# LMT01-PCB.net
KiCad netlist of a schematic drawn in EAGLE
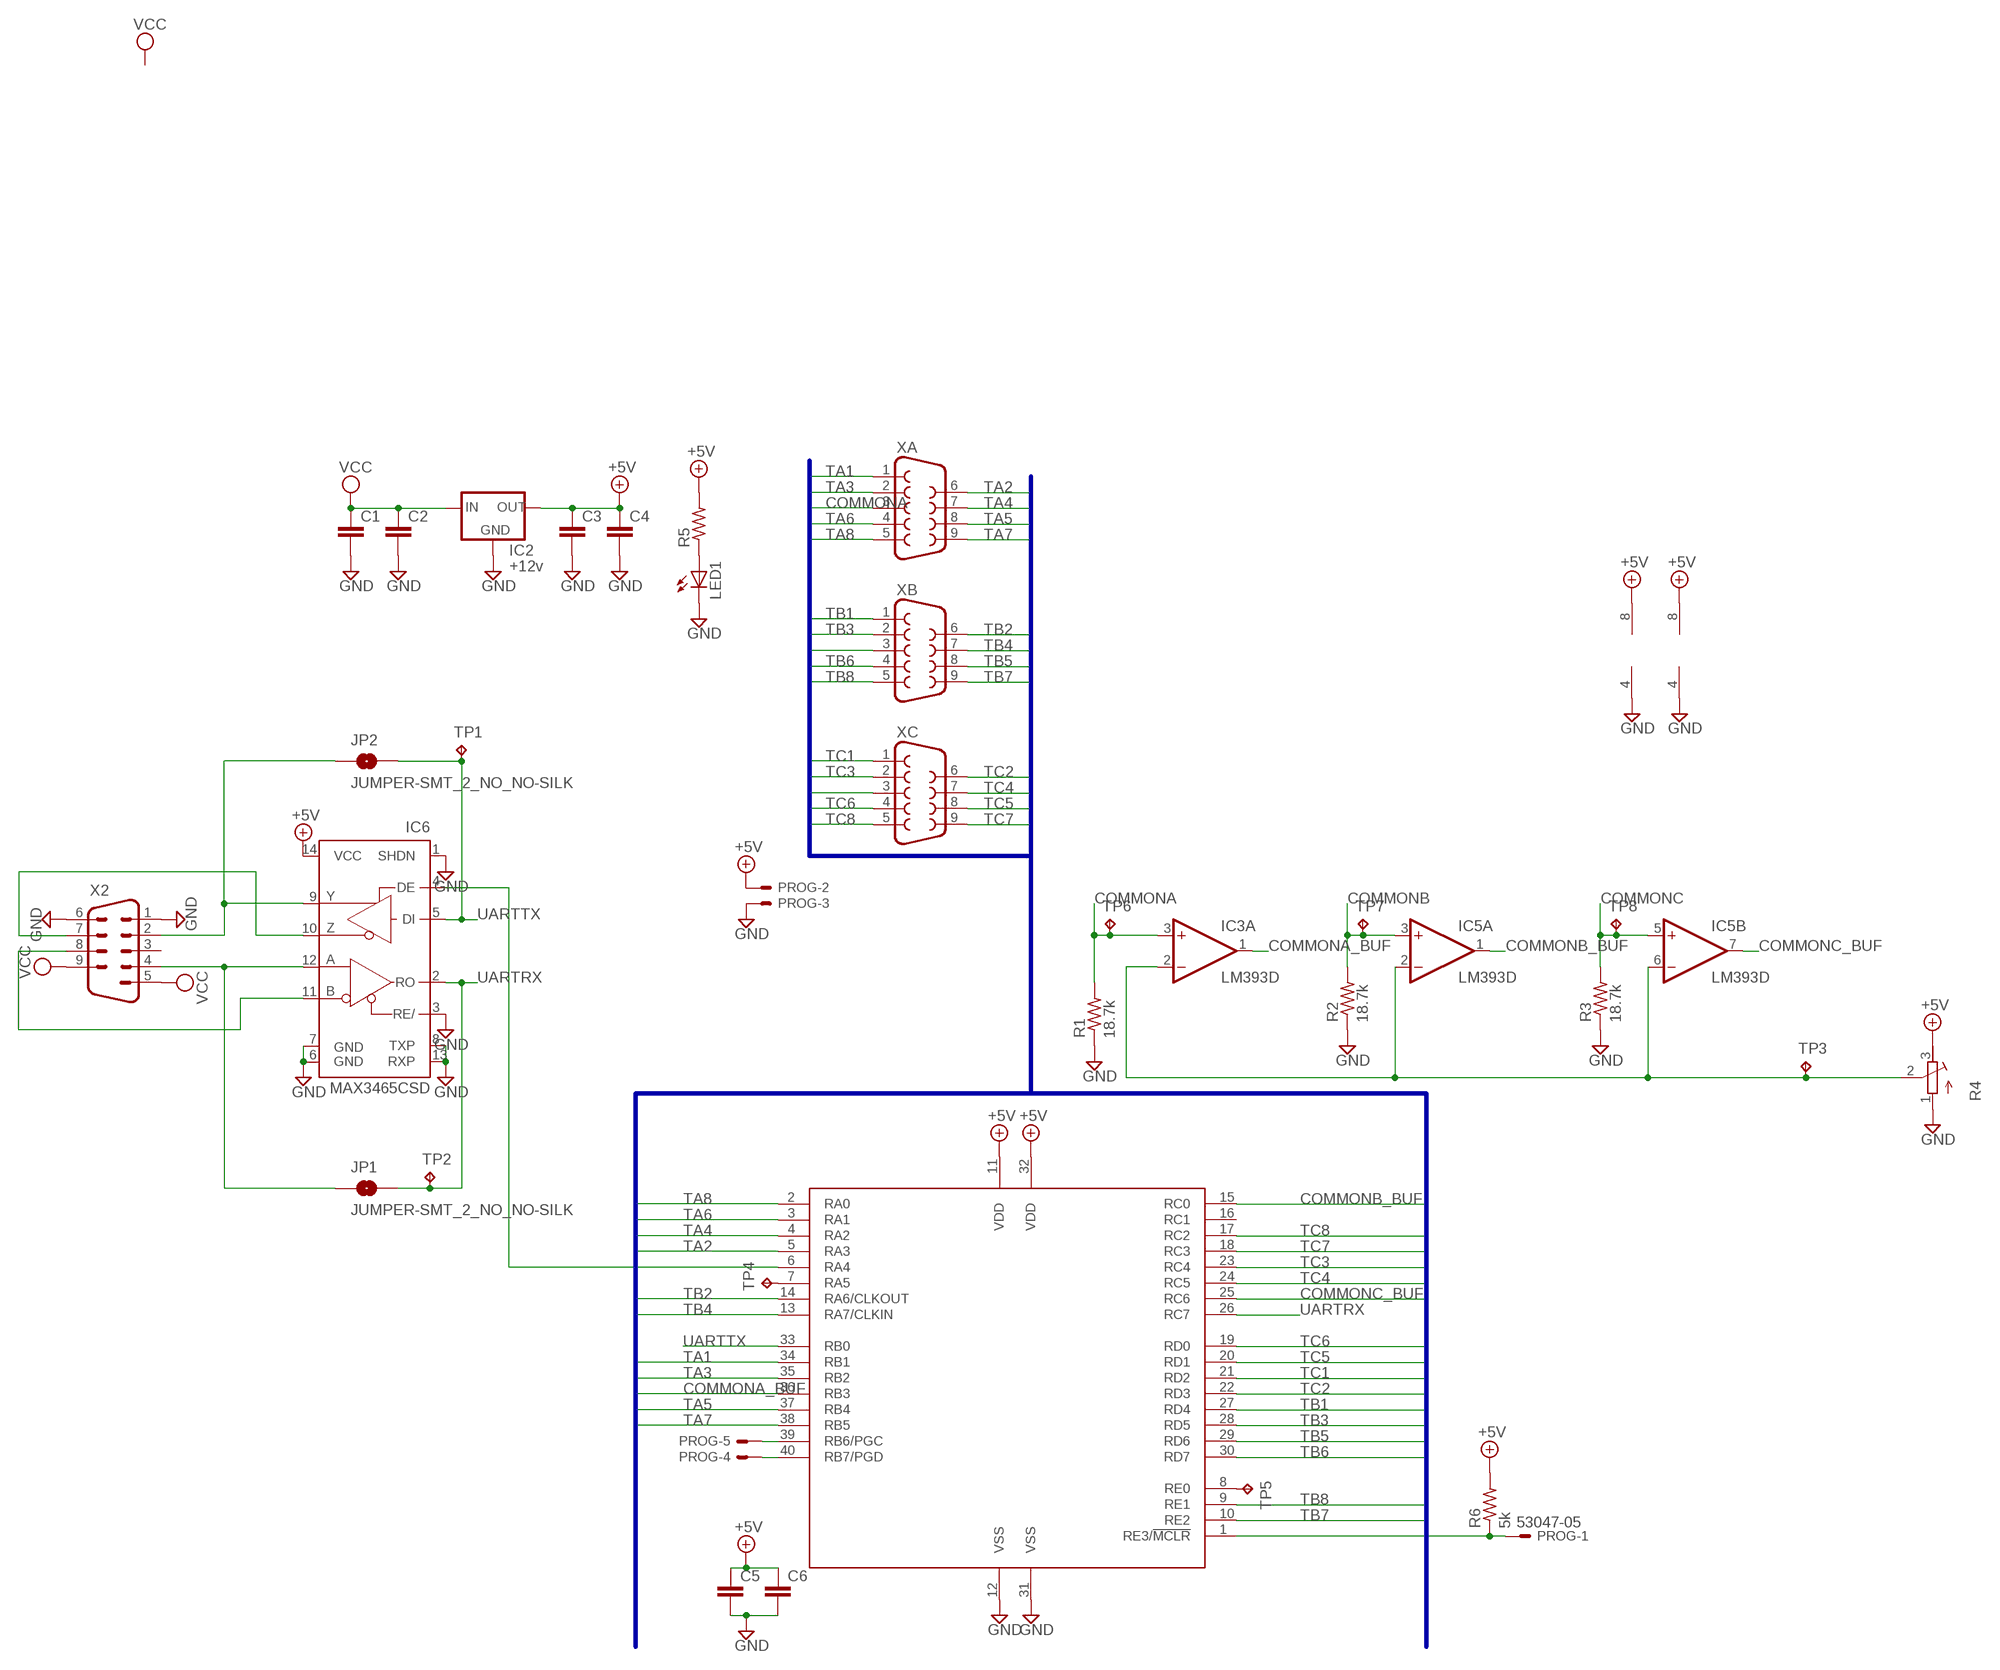
[diagram p0: schematic, sheet 1]

(export (version "E")
  (design (tool "Eeschema 10.0.6"))
  (components
    (comp (ref "C1")
      (value "C-EUC1206")
      (footprint "eagle-import:C1206")
      (libsource (lib "eagle-import") (part "C-EUC1206"))
    )
    (comp (ref "C2")
      (value "C-EUC1206")
      (footprint "eagle-import:C1206")
      (libsource (lib "eagle-import") (part "C-EUC1206"))
    )
    (comp (ref "C3")
      (value "C-EUC1206")
      (footprint "eagle-import:C1206")
      (libsource (lib "eagle-import") (part "C-EUC1206"))
    )
    (comp (ref "C4")
      (value "C-EUC1206")
      (footprint "eagle-import:C1206")
      (libsource (lib "eagle-import") (part "C-EUC1206"))
    )
    (comp (ref "C5")
      (value "C-EUC1206")
      (footprint "eagle-import:C1206")
      (libsource (lib "eagle-import") (part "C-EUC1206"))
    )
    (comp (ref "C6")
      (value "C-EUC1206")
      (footprint "eagle-import:C1206")
      (libsource (lib "eagle-import") (part "C-EUC1206"))
    )
    (comp (ref "IC1")
      (value "PIC18F47Q84")
      (footprint "eagle-import:DIL40")
      (libsource (lib "eagle-import") (part "PIC18F47Q84"))
    )
    (comp (ref "IC2")
      (value "+12v")
      (footprint "eagle-import:TO-252")
      (libsource (lib "eagle-import") (part "V_REG_78XX7812"))
    )
    (comp (ref "IC3")
      (value "LM393D")
      (footprint "eagle-import:SO08")
      (libsource (lib "eagle-import") (part "LM393D"))
    )
    (comp (ref "IC5")
      (value "LM393D")
      (footprint "eagle-import:SO08")
      (libsource (lib "eagle-import") (part "LM393D"))
    )
    (comp (ref "IC6")
      (value "MAX3465CSD")
      (footprint "eagle-import:SO14")
      (fields (field (name "MPN") "MAX3465CSD+"))
      (libsource (lib "eagle-import") (part "MAX346SD5C"))
    )
    (comp (ref "JP1")
      (value "JUMPER-SMT_2_NO_NO-SILK")
      (footprint "eagle-import:SMT-JUMPER_2_NO_NO-SILK")
      (libsource (lib "eagle-import") (part "JUMPER-SMT_2_NO_NO-SILK"))
    )
    (comp (ref "JP2")
      (value "JUMPER-SMT_2_NO_NO-SILK")
      (footprint "eagle-import:SMT-JUMPER_2_NO_NO-SILK")
      (libsource (lib "eagle-import") (part "JUMPER-SMT_2_NO_NO-SILK"))
    )
    (comp (ref "LED1")
      (value "LEDCHIPLED_1206")
      (footprint "eagle-import:CHIPLED_1206")
      (libsource (lib "eagle-import") (part "LEDCHIPLED_1206"))
    )
    (comp (ref "PROG")
      (value "53047-05")
      (footprint "eagle-import:53047-05")
      (fields (field (name "MF") "MOLEX") (field (name "MPN") "53047-0510"))
      (libsource (lib "eagle-import") (part "53?-05047"))
    )
    (comp (ref "R1")
      (value "18.7k")
      (footprint "eagle-import:R1206")
      (libsource (lib "eagle-import") (part "R-US_R1206"))
    )
    (comp (ref "R2")
      (value "18.7k")
      (footprint "eagle-import:R1206")
      (libsource (lib "eagle-import") (part "R-US_R1206"))
    )
    (comp (ref "R3")
      (value "18.7k")
      (footprint "eagle-import:R1206")
      (libsource (lib "eagle-import") (part "R-US_R1206"))
    )
    (comp (ref "R4")
      (value "R-TRIMM4G/J")
      (footprint "eagle-import:RTRIM4G_J")
      (libsource (lib "eagle-import") (part "R-TRIMM4G/J"))
    )
    (comp (ref "R5")
      (value "R-US_R1206")
      (footprint "eagle-import:R1206")
      (libsource (lib "eagle-import") (part "R-US_R1206"))
    )
    (comp (ref "R6")
      (value "5k")
      (footprint "eagle-import:R1206")
      (libsource (lib "eagle-import") (part "R-US_R1206"))
    )
    (comp (ref "TP1")
      (value "TPB1,27")
      (footprint "eagle-import:B1,27")
      (libsource (lib "eagle-import") (part "TPB1,27"))
    )
    (comp (ref "TP2")
      (value "TPB1,27")
      (footprint "eagle-import:B1,27")
      (libsource (lib "eagle-import") (part "TPB1,27"))
    )
    (comp (ref "TP3")
      (value "TPB1,27")
      (footprint "eagle-import:B1,27")
      (libsource (lib "eagle-import") (part "TPB1,27"))
    )
    (comp (ref "TP4")
      (value "TPB1,27")
      (footprint "eagle-import:B1,27")
      (libsource (lib "eagle-import") (part "TPB1,27"))
    )
    (comp (ref "TP5")
      (value "TPB1,27")
      (footprint "eagle-import:B1,27")
      (libsource (lib "eagle-import") (part "TPB1,27"))
    )
    (comp (ref "TP6")
      (value "TPB1,27")
      (footprint "eagle-import:B1,27")
      (libsource (lib "eagle-import") (part "TPB1,27"))
    )
    (comp (ref "TP7")
      (value "TPB1,27")
      (footprint "eagle-import:B1,27")
      (libsource (lib "eagle-import") (part "TPB1,27"))
    )
    (comp (ref "TP8")
      (value "TPB1,27")
      (footprint "eagle-import:B1,27")
      (libsource (lib "eagle-import") (part "TPB1,27"))
    )
    (comp (ref "X2")
      (value "M09HP")
      (footprint "eagle-import:M09HP")
      (libsource (lib "eagle-import") (part "M09HP"))
    )
    (comp (ref "XA")
      (value "F09HP")
      (footprint "eagle-import:F09HP")
      (libsource (lib "eagle-import") (part "F09HP"))
    )
    (comp (ref "XB")
      (value "F09HP")
      (footprint "eagle-import:F09HP")
      (libsource (lib "eagle-import") (part "F09HP"))
    )
    (comp (ref "XC")
      (value "F09HP")
      (footprint "eagle-import:F09HP")
      (libsource (lib "eagle-import") (part "F09HP"))
    )
  )
  (nets
    (net (code "1") (name "+5V") (class "Default")
      (node (ref "C3") (pin "1") (pinfunction "1_1") (pintype "passive"))
      (node (ref "C4") (pin "1") (pinfunction "1_1") (pintype "passive"))
      (node (ref "C5") (pin "1") (pinfunction "1_1") (pintype "passive"))
      (node (ref "C6") (pin "1") (pinfunction "1_1") (pintype "passive"))
      (node (ref "IC1") (pin "11") (pinfunction "VDD_11") (pintype "bidirectional"))
      (node (ref "IC1") (pin "32") (pinfunction "VDD_32") (pintype "bidirectional"))
      (node (ref "IC2") (pin "2") (pinfunction "OUT_2") (pintype "passive"))
      (node (ref "IC3") (pin "8") (pinfunction "V+_8") (pintype "power_in"))
      (node (ref "IC5") (pin "8") (pinfunction "V+_8") (pintype "power_in"))
      (node (ref "IC6") (pin "14") (pinfunction "VCC_14") (pintype "power_in"))
      (node (ref "PROG") (pin "2") (pinfunction "S_2") (pintype "passive"))
      (node (ref "R4") (pin "3") (pinfunction "E_3") (pintype "passive"))
      (node (ref "R5") (pin "2") (pinfunction "2_2") (pintype "passive"))
      (node (ref "R6") (pin "2") (pinfunction "2_2") (pintype "passive"))
    )
    (net (code "2") (name "/COMMONA") (class "Default")
      (node (ref "IC3") (pin "3") (pinfunction "+IN_3") (pintype "input"))
      (node (ref "R1") (pin "2") (pinfunction "2_2") (pintype "passive"))
      (node (ref "TP6") (pin "TP") (pinfunction "TP_TP") (pintype "input"))
      (node (ref "XA") (pin "3") (pinfunction "3_3") (pintype "passive"))
    )
    (net (code "3") (name "/COMMONA_BUF") (class "Default")
      (node (ref "IC1") (pin "36") (pinfunction "RB3_36") (pintype "bidirectional"))
      (node (ref "IC3") (pin "1") (pinfunction "OUT_1") (pintype "output"))
    )
    (net (code "4") (name "/COMMONB") (class "Default")
      (node (ref "IC5") (pin "3") (pinfunction "+IN_3") (pintype "input"))
      (node (ref "R2") (pin "2") (pinfunction "2_2") (pintype "passive"))
      (node (ref "TP7") (pin "TP") (pinfunction "TP_TP") (pintype "input"))
      (node (ref "XB") (pin "3") (pinfunction "3_3") (pintype "passive"))
    )
    (net (code "5") (name "/COMMONB_BUF") (class "Default")
      (node (ref "IC1") (pin "15") (pinfunction "RC0_15") (pintype "bidirectional"))
      (node (ref "IC5") (pin "1") (pinfunction "OUT_1") (pintype "output"))
    )
    (net (code "6") (name "/COMMONC") (class "Default")
      (node (ref "IC5") (pin "5") (pinfunction "+IN_5") (pintype "input"))
      (node (ref "R3") (pin "2") (pinfunction "2_2") (pintype "passive"))
      (node (ref "TP8") (pin "TP") (pinfunction "TP_TP") (pintype "input"))
      (node (ref "XC") (pin "3") (pinfunction "3_3") (pintype "passive"))
    )
    (net (code "7") (name "/COMMONC_BUF") (class "Default")
      (node (ref "IC1") (pin "25") (pinfunction "RC6_25") (pintype "bidirectional"))
      (node (ref "IC5") (pin "7") (pinfunction "OUT_7") (pintype "output"))
    )
    (net (code "8") (name "/TA1") (class "Default")
      (node (ref "IC1") (pin "34") (pinfunction "RB1_34") (pintype "bidirectional"))
      (node (ref "XA") (pin "1") (pinfunction "1_1") (pintype "passive"))
    )
    (net (code "9") (name "/TA2") (class "Default")
      (node (ref "IC1") (pin "5") (pinfunction "RA3_5") (pintype "bidirectional"))
      (node (ref "XA") (pin "6") (pinfunction "6_6") (pintype "passive"))
    )
    (net (code "10") (name "/TA3") (class "Default")
      (node (ref "IC1") (pin "35") (pinfunction "RB2_35") (pintype "bidirectional"))
      (node (ref "XA") (pin "2") (pinfunction "2_2") (pintype "passive"))
    )
    (net (code "11") (name "/TA4") (class "Default")
      (node (ref "IC1") (pin "4") (pinfunction "RA2_4") (pintype "bidirectional"))
      (node (ref "XA") (pin "7") (pinfunction "7_7") (pintype "passive"))
    )
    (net (code "12") (name "/TA5") (class "Default")
      (node (ref "IC1") (pin "37") (pinfunction "RB4_37") (pintype "bidirectional"))
      (node (ref "XA") (pin "8") (pinfunction "8_8") (pintype "passive"))
    )
    (net (code "13") (name "/TA6") (class "Default")
      (node (ref "IC1") (pin "3") (pinfunction "RA1_3") (pintype "bidirectional"))
      (node (ref "XA") (pin "4") (pinfunction "4_4") (pintype "passive"))
    )
    (net (code "14") (name "/TA7") (class "Default")
      (node (ref "IC1") (pin "38") (pinfunction "RB5_38") (pintype "bidirectional"))
      (node (ref "XA") (pin "9") (pinfunction "9_9") (pintype "passive"))
    )
    (net (code "15") (name "/TA8") (class "Default")
      (node (ref "IC1") (pin "2") (pinfunction "RA0_2") (pintype "bidirectional"))
      (node (ref "XA") (pin "5") (pinfunction "5_5") (pintype "passive"))
    )
    (net (code "16") (name "/TB1") (class "Default")
      (node (ref "IC1") (pin "27") (pinfunction "RD4_27") (pintype "bidirectional"))
      (node (ref "XB") (pin "1") (pinfunction "1_1") (pintype "passive"))
    )
    (net (code "17") (name "/TB2") (class "Default")
      (node (ref "IC1") (pin "14") (pinfunction "RA6/CLKOUT_14") (pintype "bidirectional"))
      (node (ref "XB") (pin "6") (pinfunction "6_6") (pintype "passive"))
    )
    (net (code "18") (name "/TB3") (class "Default")
      (node (ref "IC1") (pin "28") (pinfunction "RD5_28") (pintype "bidirectional"))
      (node (ref "XB") (pin "2") (pinfunction "2_2") (pintype "passive"))
    )
    (net (code "19") (name "/TB4") (class "Default")
      (node (ref "IC1") (pin "13") (pinfunction "RA7/CLKIN_13") (pintype "bidirectional"))
      (node (ref "XB") (pin "7") (pinfunction "7_7") (pintype "passive"))
    )
    (net (code "20") (name "/TB5") (class "Default")
      (node (ref "IC1") (pin "29") (pinfunction "RD6_29") (pintype "bidirectional"))
      (node (ref "XB") (pin "8") (pinfunction "8_8") (pintype "passive"))
    )
    (net (code "21") (name "/TB6") (class "Default")
      (node (ref "IC1") (pin "30") (pinfunction "RD7_30") (pintype "bidirectional"))
      (node (ref "XB") (pin "4") (pinfunction "4_4") (pintype "passive"))
    )
    (net (code "22") (name "/TB7") (class "Default")
      (node (ref "IC1") (pin "10") (pinfunction "RE2_10") (pintype "bidirectional"))
      (node (ref "XB") (pin "9") (pinfunction "9_9") (pintype "passive"))
    )
    (net (code "23") (name "/TB8") (class "Default")
      (node (ref "IC1") (pin "9") (pinfunction "RE1_9") (pintype "bidirectional"))
      (node (ref "XB") (pin "5") (pinfunction "5_5") (pintype "passive"))
    )
    (net (code "24") (name "/TC1") (class "Default")
      (node (ref "IC1") (pin "21") (pinfunction "RD2_21") (pintype "bidirectional"))
      (node (ref "XC") (pin "1") (pinfunction "1_1") (pintype "passive"))
    )
    (net (code "25") (name "/TC2") (class "Default")
      (node (ref "IC1") (pin "22") (pinfunction "RD3_22") (pintype "bidirectional"))
      (node (ref "XC") (pin "6") (pinfunction "6_6") (pintype "passive"))
    )
    (net (code "26") (name "/TC3") (class "Default")
      (node (ref "IC1") (pin "23") (pinfunction "RC4_23") (pintype "bidirectional"))
      (node (ref "XC") (pin "2") (pinfunction "2_2") (pintype "passive"))
    )
    (net (code "27") (name "/TC4") (class "Default")
      (node (ref "IC1") (pin "24") (pinfunction "RC5_24") (pintype "bidirectional"))
      (node (ref "XC") (pin "7") (pinfunction "7_7") (pintype "passive"))
    )
    (net (code "28") (name "/TC5") (class "Default")
      (node (ref "IC1") (pin "20") (pinfunction "RD1_20") (pintype "bidirectional"))
      (node (ref "XC") (pin "8") (pinfunction "8_8") (pintype "passive"))
    )
    (net (code "29") (name "/TC6") (class "Default")
      (node (ref "IC1") (pin "19") (pinfunction "RD0_19") (pintype "bidirectional"))
      (node (ref "XC") (pin "4") (pinfunction "4_4") (pintype "passive"))
    )
    (net (code "30") (name "/TC7") (class "Default")
      (node (ref "IC1") (pin "18") (pinfunction "RC3_18") (pintype "bidirectional"))
      (node (ref "XC") (pin "9") (pinfunction "9_9") (pintype "passive"))
    )
    (net (code "31") (name "/TC8") (class "Default")
      (node (ref "IC1") (pin "17") (pinfunction "RC2_17") (pintype "bidirectional"))
      (node (ref "XC") (pin "5") (pinfunction "5_5") (pintype "passive"))
    )
    (net (code "32") (name "/UARTRX") (class "Default")
      (node (ref "IC1") (pin "26") (pinfunction "RC7_26") (pintype "bidirectional"))
      (node (ref "IC6") (pin "2") (pinfunction "RO_2") (pintype "output"))
      (node (ref "JP1") (pin "2") (pinfunction "2_2") (pintype "passive"))
      (node (ref "TP2") (pin "TP") (pinfunction "TP_TP") (pintype "input"))
    )
    (net (code "33") (name "/UARTTX") (class "Default")
      (node (ref "IC1") (pin "33") (pinfunction "RB0_33") (pintype "bidirectional"))
      (node (ref "IC6") (pin "5") (pinfunction "DI_5") (pintype "input"))
      (node (ref "JP2") (pin "2") (pinfunction "2_2") (pintype "passive"))
      (node (ref "TP1") (pin "TP") (pinfunction "TP_TP") (pintype "input"))
    )
    (net (code "34") (name "GND") (class "Default")
      (node (ref "C1") (pin "2") (pinfunction "2_2") (pintype "passive"))
      (node (ref "C2") (pin "2") (pinfunction "2_2") (pintype "passive"))
      (node (ref "C3") (pin "2") (pinfunction "2_2") (pintype "passive"))
      (node (ref "C4") (pin "2") (pinfunction "2_2") (pintype "passive"))
      (node (ref "C5") (pin "2") (pinfunction "2_2") (pintype "passive"))
      (node (ref "C6") (pin "2") (pinfunction "2_2") (pintype "passive"))
      (node (ref "IC1") (pin "12") (pinfunction "VSS_12") (pintype "bidirectional"))
      (node (ref "IC1") (pin "31") (pinfunction "VSS_31") (pintype "bidirectional"))
      (node (ref "IC2") (pin "3") (pinfunction "GND_3") (pintype "input"))
      (node (ref "IC3") (pin "4") (pinfunction "V-_4") (pintype "power_in"))
      (node (ref "IC5") (pin "4") (pinfunction "V-_4") (pintype "power_in"))
      (node (ref "IC6") (pin "1") (pinfunction "SHDN_1") (pintype "input"))
      (node (ref "IC6") (pin "13") (pinfunction "RXP_13") (pintype "passive"))
      (node (ref "IC6") (pin "3") (pinfunction "RE/_3") (pintype "input"))
      (node (ref "IC6") (pin "6") (pinfunction "GND_6") (pintype "power_in"))
      (node (ref "IC6") (pin "7") (pinfunction "GND_7") (pintype "power_in"))
      (node (ref "IC6") (pin "8") (pinfunction "TXP_8") (pintype "passive"))
      (node (ref "LED1") (pin "C") (pinfunction "C_C") (pintype "passive"))
      (node (ref "PROG") (pin "3") (pinfunction "S_3") (pintype "passive"))
      (node (ref "R1") (pin "1") (pinfunction "1_1") (pintype "passive"))
      (node (ref "R2") (pin "1") (pinfunction "1_1") (pintype "passive"))
      (node (ref "R3") (pin "1") (pinfunction "1_1") (pintype "passive"))
      (node (ref "R4") (pin "1") (pinfunction "A_1") (pintype "passive"))
      (node (ref "X2") (pin "1") (pinfunction "1_1") (pintype "passive"))
      (node (ref "X2") (pin "6") (pinfunction "6_6") (pintype "passive"))
    )
    (net (code "35") (name "Net-(IC1-RA4)") (class "Default")
      (node (ref "IC1") (pin "6") (pinfunction "RA4_6") (pintype "bidirectional"))
      (node (ref "IC6") (pin "4") (pinfunction "DE_4") (pintype "input"))
    )
    (net (code "36") (name "Net-(IC1-RA5)") (class "Default")
      (node (ref "IC1") (pin "7") (pinfunction "RA5_7") (pintype "bidirectional"))
      (node (ref "TP4") (pin "TP") (pinfunction "TP_TP") (pintype "input"))
    )
    (net (code "37") (name "Net-(IC1-RB6{slash}PGC)") (class "Default")
      (node (ref "IC1") (pin "39") (pinfunction "RB6/PGC_39") (pintype "bidirectional"))
      (node (ref "PROG") (pin "5") (pinfunction "S_5") (pintype "passive"))
    )
    (net (code "38") (name "Net-(IC1-RB7{slash}PGD)") (class "Default")
      (node (ref "IC1") (pin "40") (pinfunction "RB7/PGD_40") (pintype "bidirectional"))
      (node (ref "PROG") (pin "4") (pinfunction "S_4") (pintype "passive"))
    )
    (net (code "39") (name "Net-(IC1-RE0)") (class "Default")
      (node (ref "IC1") (pin "8") (pinfunction "RE0_8") (pintype "bidirectional"))
      (node (ref "TP5") (pin "TP") (pinfunction "TP_TP") (pintype "input"))
    )
    (net (code "40") (name "Net-(IC1-RE3{slash}~{MCLR})") (class "Default")
      (node (ref "IC1") (pin "1") (pinfunction "RE3/~{MCLR}_1") (pintype "bidirectional"))
      (node (ref "PROG") (pin "1") (pinfunction "S_1") (pintype "passive"))
      (node (ref "R6") (pin "1") (pinfunction "1_1") (pintype "passive"))
    )
    (net (code "41") (name "Net-(IC3A--IN)") (class "Default")
      (node (ref "IC3") (pin "2") (pinfunction "-IN_2") (pintype "input"))
      (node (ref "IC5") (pin "2") (pinfunction "-IN_2") (pintype "input"))
      (node (ref "IC5") (pin "6") (pinfunction "-IN_6") (pintype "input"))
      (node (ref "R4") (pin "2") (pinfunction "S_2") (pintype "passive"))
      (node (ref "TP3") (pin "TP") (pinfunction "TP_TP") (pintype "input"))
    )
    (net (code "42") (name "Net-(IC6-A)") (class "Default")
      (node (ref "IC6") (pin "12") (pinfunction "A_12") (pintype "input"))
      (node (ref "JP1") (pin "1") (pinfunction "1_1") (pintype "passive"))
      (node (ref "X2") (pin "4") (pinfunction "4_4") (pintype "passive"))
    )
    (net (code "43") (name "Net-(IC6-B)") (class "Default")
      (node (ref "IC6") (pin "11") (pinfunction "B_11") (pintype "input"))
      (node (ref "X2") (pin "8") (pinfunction "8_8") (pintype "passive"))
    )
    (net (code "44") (name "Net-(IC6-Y)") (class "Default")
      (node (ref "IC6") (pin "9") (pinfunction "Y_9") (pintype "output"))
      (node (ref "JP2") (pin "1") (pinfunction "1_1") (pintype "passive"))
      (node (ref "X2") (pin "2") (pinfunction "2_2") (pintype "passive"))
    )
    (net (code "45") (name "Net-(IC6-Z)") (class "Default")
      (node (ref "IC6") (pin "10") (pinfunction "Z_10") (pintype "output"))
      (node (ref "X2") (pin "7") (pinfunction "7_7") (pintype "passive"))
    )
    (net (code "46") (name "Net-(LED1-PadA)") (class "Default")
      (node (ref "LED1") (pin "A") (pinfunction "A_A") (pintype "passive"))
      (node (ref "R5") (pin "1") (pinfunction "1_1") (pintype "passive"))
    )
    (net (code "47") (name "VCC") (class "Default")
      (node (ref "C1") (pin "1") (pinfunction "1_1") (pintype "passive"))
      (node (ref "C2") (pin "1") (pinfunction "1_1") (pintype "passive"))
      (node (ref "IC2") (pin "1") (pinfunction "IN_1") (pintype "input"))
      (node (ref "X2") (pin "5") (pinfunction "5_5") (pintype "passive"))
      (node (ref "X2") (pin "9") (pinfunction "9_9") (pintype "passive"))
    )
    (net (code "48") (name "unconnected-(IC1-RC1-Pad16)") (class "Default")
      (node (ref "IC1") (pin "16") (pinfunction "RC1_16") (pintype "bidirectional"))
    )
    (net (code "49") (name "unconnected-(X2-Pad3)") (class "Default")
      (node (ref "X2") (pin "3") (pinfunction "3_3") (pintype "passive"))
    )
  )
)
